# amplifier.net
KiCad netlist of a schematic drawn in Altium Designer
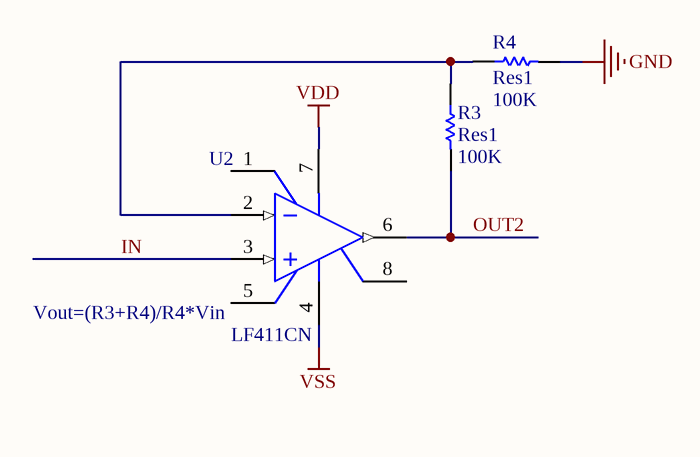
[diagram p0: amplifier.SchDoc]

(export (version "E")
  (design (tool "Eeschema 10.0.6"))
  (components
    (comp (ref "R3")
      (value "Res1")
      (footprint "AXIAL-0.3")
      (description "Resistor")
      (fields (field (name "ALTIUM_VALUE") "100K") (field (name "PUBLISHER") "Altium Limited"))
      (libsource (lib "Miscellaneous Devices") (part "Res1"))
    )
    (comp (ref "R4")
      (value "Res1")
      (footprint "AXIAL-0.3")
      (description "Resistor")
      (fields (field (name "ALTIUM_VALUE") "100K") (field (name "PUBLISHER") "Altium Limited"))
      (libsource (lib "Miscellaneous Devices") (part "Res1"))
    )
    (comp (ref "U2")
      (value "LF411CN")
      (footprint "N08E")
      (description "Low Offset, Low Drift JFET Input Operational Amplifier, 8-pin MDIP")
      (fields
        (field (name "MANUFACTURER") "National Semiconductor")
        (field (name "PUBLISHER") "Altium Limited")
      )
      (libsource (lib "NSC Amplifier") (part "LF411CN"))
    )
  )
  (nets
    (net (code "1") (name "/IN") (class "Default")
      (node (ref "U2") (pin "3") (pinfunction "IN+_3") (pintype "input"))
    )
    (net (code "2") (name "/OUT2") (class "Default")
      (node (ref "R3") (pin "2") (pinfunction "2_2") (pintype "passive"))
      (node (ref "U2") (pin "6") (pinfunction "OUT_6") (pintype "output"))
    )
    (net (code "3") (name "GND") (class "Default")
      (node (ref "R4") (pin "2") (pinfunction "2_2") (pintype "passive"))
    )
    (net (code "4") (name "Net-(U2-IN-)") (class "Default")
      (node (ref "R3") (pin "1") (pinfunction "1_1") (pintype "passive"))
      (node (ref "R4") (pin "1") (pinfunction "1_1") (pintype "passive"))
      (node (ref "U2") (pin "2") (pinfunction "IN-_2") (pintype "input"))
    )
    (net (code "5") (name "VDD") (class "Default")
      (node (ref "U2") (pin "7") (pinfunction "V+_7") (pintype "power_in"))
    )
    (net (code "6") (name "VSS") (class "Default")
      (node (ref "U2") (pin "4") (pinfunction "V-_4") (pintype "power_in"))
    )
    (net (code "7") (name "unconnected-(U2-BAL-Pad1)") (class "Default")
      (node (ref "U2") (pin "1") (pinfunction "BAL_1") (pintype "passive"))
    )
    (net (code "8") (name "unconnected-(U2-BAL-Pad5)") (class "Default")
      (node (ref "U2") (pin "5") (pinfunction "BAL_5") (pintype "passive"))
    )
    (net (code "9") (name "unconnected-(U2-NC-Pad8)") (class "Default")
      (node (ref "U2") (pin "8") (pinfunction "NC_8") (pintype "passive"))
    )
  )
)
